# Fri3D_2020_ESP32.net
KiCad netlist of a schematic drawn in Altium Designer
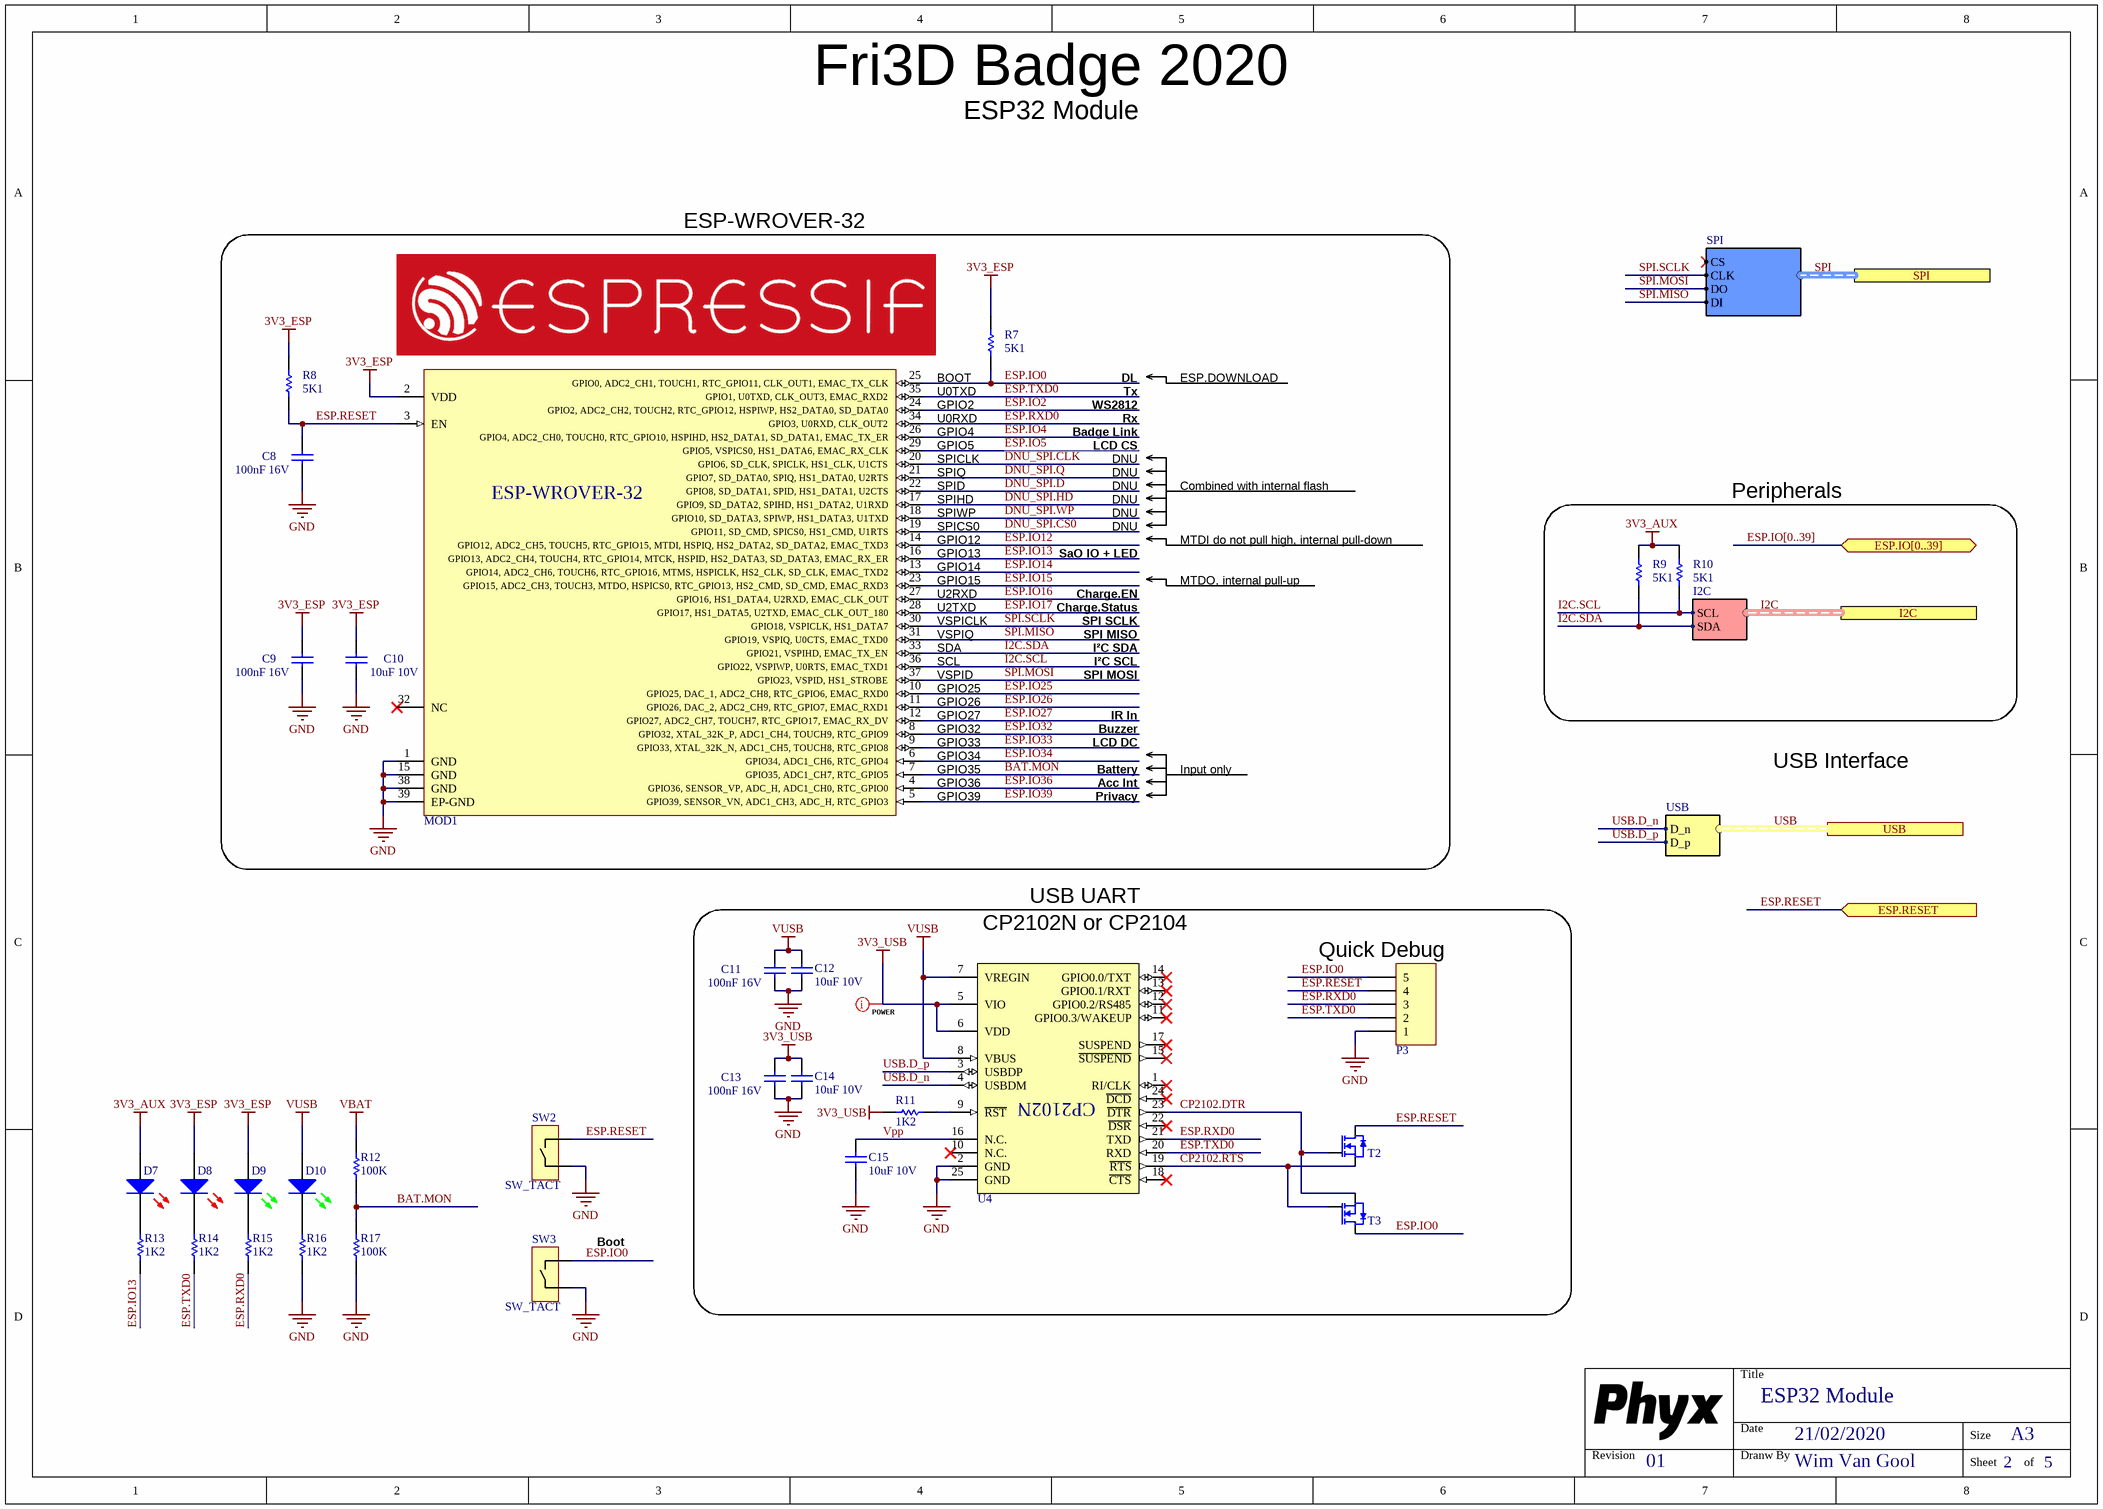
[diagram p0: Fri3D_2020_ESP32.SchDoc]

(export (version "E")
  (design (tool "Eeschema 10.0.6"))
  (components
    (comp (ref "C8")
      (value "100nF 16V")
      (footprint "C0603_N")
      (description "Capacitor Ceramic")
      (libsource (lib "Phyx_Components") (part "CAP_CERAMIC"))
    )
    (comp (ref "C9")
      (value "100nF 16V")
      (footprint "C0603_N")
      (description "Capacitor Ceramic")
      (libsource (lib "Phyx_Components") (part "CAP_CERAMIC"))
    )
    (comp (ref "C10")
      (value "10uF 10V")
      (footprint "C0805_N")
      (description "Capacitor Ceramic")
      (fields (field (name "Comment") "CAP_CERAMIC"))
      (libsource (lib "Phyx_Components") (part "CAP_CERAMIC"))
    )
    (comp (ref "C11")
      (value "100nF 16V")
      (footprint "C0603_N")
      (description "Capacitor Ceramic")
      (libsource (lib "Phyx_Components") (part "CAP_CERAMIC"))
    )
    (comp (ref "C12")
      (value "10uF 10V")
      (footprint "C0805_N")
      (description "Capacitor Ceramic")
      (fields (field (name "Comment") "CAP_CERAMIC"))
      (libsource (lib "Phyx_Components") (part "CAP_CERAMIC"))
    )
    (comp (ref "C13")
      (value "100nF 16V")
      (footprint "C0603_N")
      (description "Capacitor Ceramic")
      (libsource (lib "Phyx_Components") (part "CAP_CERAMIC"))
    )
    (comp (ref "C14")
      (value "10uF 10V")
      (footprint "C0805_N")
      (description "Capacitor Ceramic")
      (fields (field (name "Comment") "CAP_CERAMIC"))
      (libsource (lib "Phyx_Components") (part "CAP_CERAMIC"))
    )
    (comp (ref "C15")
      (value "10uF 10V")
      (footprint "C0805_N")
      (description "Capacitor Ceramic")
      (fields (field (name "Comment") "CAP_CERAMIC"))
      (libsource (lib "Phyx_Components") (part "CAP_CERAMIC"))
    )
    (comp (ref "D7")
      (value "Default 0805 Red LED")
      (footprint "LED_0805_RD")
      (description "=Description")
      (libsource (lib "Phyx_Components") (part "LED_RED"))
    )
    (comp (ref "D8")
      (value "Default 0805 Red LED")
      (footprint "LED_0805_RD")
      (description "=Description")
      (libsource (lib "Phyx_Components") (part "LED_RED"))
    )
    (comp (ref "D9")
      (value "Default 0805 Green LED")
      (footprint "LED_0805_GR")
      (description "=Description")
      (libsource (lib "Phyx_Components") (part "LED_GREEN"))
    )
    (comp (ref "D10")
      (value "Default 0805 Green LED")
      (footprint "LED_0805_GR")
      (description "=Description")
      (libsource (lib "Phyx_Components") (part "LED_GREEN"))
    )
    (comp (ref "MOD1")
      (value "ESP-32 based ESP-WROVER-32")
      (footprint "ESP-WROVER-32")
      (description "WiFi # MOD ESP-WROVER-32")
      (libsource (lib "Phyx_Components") (part "ESP-WROVER-32"))
    )
    (comp (ref "P3")
      (value "Header 1.0mm RA Shrouded 5")
      (footprint "WE_665105131822")
      (libsource (lib "Phyx_Components") (part "Header 5"))
    )
    (comp (ref "R7")
      (value "5K1")
      (footprint "R0603_N")
      (fields (field (name "Comment") "RESISTOR"))
      (libsource (lib "Phyx_Components") (part "RESISTOR"))
    )
    (comp (ref "R8")
      (value "5K1")
      (footprint "R0603_N")
      (fields (field (name "Comment") "RESISTOR"))
      (libsource (lib "Phyx_Components") (part "RESISTOR"))
    )
    (comp (ref "R9")
      (value "5K1")
      (footprint "R0603_N")
      (fields (field (name "Comment") "RESISTOR"))
      (libsource (lib "Phyx_Components") (part "RESISTOR"))
    )
    (comp (ref "R10")
      (value "5K1")
      (footprint "R0603_N")
      (fields (field (name "Comment") "RESISTOR"))
      (libsource (lib "Phyx_Components") (part "RESISTOR"))
    )
    (comp (ref "R11")
      (value "1K2")
      (footprint "R0603_N")
      (fields (field (name "Comment") "RESISTOR"))
      (libsource (lib "Phyx_Components") (part "RESISTOR"))
    )
    (comp (ref "R12")
      (value "100K")
      (footprint "R0603_N")
      (fields (field (name "Comment") "RESISTOR"))
      (libsource (lib "Phyx_Components") (part "RESISTOR"))
    )
    (comp (ref "R13")
      (value "1K2")
      (footprint "R0603_N")
      (fields (field (name "Comment") "RESISTOR"))
      (libsource (lib "Phyx_Components") (part "RESISTOR"))
    )
    (comp (ref "R14")
      (value "1K2")
      (footprint "R0603_N")
      (fields (field (name "Comment") "RESISTOR"))
      (libsource (lib "Phyx_Components") (part "RESISTOR"))
    )
    (comp (ref "R15")
      (value "1K2")
      (footprint "R0603_N")
      (fields (field (name "Comment") "RESISTOR"))
      (libsource (lib "Phyx_Components") (part "RESISTOR"))
    )
    (comp (ref "R16")
      (value "1K2")
      (footprint "R0603_N")
      (fields (field (name "Comment") "RESISTOR"))
      (libsource (lib "Phyx_Components") (part "RESISTOR"))
    )
    (comp (ref "R17")
      (value "100K")
      (footprint "R0603_N")
      (fields (field (name "Comment") "RESISTOR"))
      (libsource (lib "Phyx_Components") (part "RESISTOR"))
    )
    (comp (ref "SW2")
      (value "SW_TACT")
      (footprint "WE_430181038816")
      (libsource (lib "Phyx_Components") (part "SW_TACT"))
    )
    (comp (ref "SW3")
      (value "SW_TACT")
      (footprint "WE_430181038816")
      (libsource (lib "Phyx_Components") (part "SW_TACT"))
    )
    (comp (ref "T2")
      (value "0.2A N-Ch MOSFET Vgs 3.2")
      (footprint "SOT23-3")
      (libsource (lib "Phyx_Components") (part "N_MOSFET_GSD"))
    )
    (comp (ref "T3")
      (value "0.2A N-Ch MOSFET Vgs 3.2")
      (footprint "SOT23-3")
      (libsource (lib "Phyx_Components") (part "N_MOSFET_GSD"))
    )
    (comp (ref "U4")
      (value "USB to UART 3.3-5V")
      (footprint "QFN_24")
      (description "=Description")
      (libsource (lib "Phyx_Components") (part "CP2102N_QFN24"))
    )
  )
  (nets
    (net (code "26") (name "/BAT.MON") (class "Default")
      (node (ref "MOD1") (pin "7") (pinfunction "GPIO35,_ADC1_CH7,_RTC_GPIO5_7") (pintype "input"))
      (node (ref "R12") (pin "2") (pinfunction "2_2") (pintype "passive"))
      (node (ref "R17") (pin "1") (pinfunction "1_1") (pintype "passive"))
    )
    (net (code "27") (name "/CP2102.DTR") (class "Default")
      (node (ref "T2") (pin "1") (pinfunction "G_1") (pintype "passive"))
      (node (ref "T3") (pin "2") (pinfunction "S_2") (pintype "passive"))
      (node (ref "U4") (pin "23") (pinfunction "~{DTR}_23") (pintype "output"))
    )
    (net (code "28") (name "/CP2102.RTS") (class "Default")
      (node (ref "T2") (pin "2") (pinfunction "S_2") (pintype "passive"))
      (node (ref "T3") (pin "1") (pinfunction "G_1") (pintype "passive"))
      (node (ref "U4") (pin "19") (pinfunction "~{RTS}_19") (pintype "output"))
    )
    (net (code "29") (name "/DNU_SPI.CLK") (class "Default")
      (node (ref "MOD1") (pin "20") (pinfunction "GPIO6,_SD_CLK,_SPICLK,_HS1_CLK,_U1CTS_20") (pintype "bidirectional"))
    )
    (net (code "30") (name "/DNU_SPI.CS0") (class "Default")
      (node (ref "MOD1") (pin "19") (pinfunction "GPIO11,_SD_CMD,_SPICS0,_HS1_CMD,_U1RTS_19") (pintype "bidirectional"))
    )
    (net (code "31") (name "/DNU_SPI.D") (class "Default")
      (node (ref "MOD1") (pin "22") (pinfunction "GPIO8,_SD_DATA1,_SPID,_HS1_DATA1,_U2CTS_22") (pintype "bidirectional"))
    )
    (net (code "32") (name "/DNU_SPI.HD") (class "Default")
      (node (ref "MOD1") (pin "17") (pinfunction "GPIO9,_SD_DATA2,_SPIHD,_HS1_DATA2,_U1RXD_17") (pintype "bidirectional"))
    )
    (net (code "33") (name "/DNU_SPI.Q") (class "Default")
      (node (ref "MOD1") (pin "21") (pinfunction "GPIO7,_SD_DATA0,_SPIQ,_HS1_DATA0,_U2RTS_21") (pintype "bidirectional"))
    )
    (net (code "34") (name "/DNU_SPI.WP") (class "Default")
      (node (ref "MOD1") (pin "18") (pinfunction "GPIO10,_SD_DATA3,_SPIWP,_HS1_DATA3,_U1TXD_18") (pintype "bidirectional"))
    )
    (net (code "35") (name "/ESP.IO0") (class "Default")
      (node (ref "MOD1") (pin "25") (pinfunction "GPIO0,_ADC2_CH1,_TOUCH1,_RTC_GPIO11,_CLK_OUT1,_EMAC_TX_CLK_25") (pintype "bidirectional"))
      (node (ref "P3") (pin "5") (pinfunction "5_5") (pintype "passive"))
      (node (ref "R7") (pin "2") (pinfunction "2_2") (pintype "passive"))
      (node (ref "SW3") (pin "1") (pinfunction "1_1") (pintype "passive"))
      (node (ref "T3") (pin "3") (pinfunction "D_3") (pintype "passive"))
    )
    (net (code "36") (name "/ESP.IO2") (class "Default")
      (node (ref "MOD1") (pin "24") (pinfunction "GPIO2,_ADC2_CH2,_TOUCH2,_RTC_GPIO12,_HSPIWP,_HS2_DATA0,_SD_DATA0_24") (pintype "bidirectional"))
    )
    (net (code "37") (name "/ESP.IO4") (class "Default")
      (node (ref "MOD1") (pin "26") (pinfunction "GPIO4,_ADC2_CH0,_TOUCH0,_RTC_GPIO10,_HSPIHD,_HS2_DATA1,_SD_DATA1,_EMAC_TX_ER_26") (pintype "bidirectional"))
    )
    (net (code "38") (name "/ESP.IO5") (class "Default")
      (node (ref "MOD1") (pin "29") (pinfunction "GPIO5,_VSPICS0,_HS1_DATA6,_EMAC_RX_CLK_29") (pintype "bidirectional"))
    )
    (net (code "39") (name "/ESP.IO12") (class "Default")
      (node (ref "MOD1") (pin "14") (pinfunction "GPIO12,_ADC2_CH5,_TOUCH5,_RTC_GPIO15,_MTDI,_HSPIQ,_HS2_DATA2,_SD_DATA2,_EMAC_TXD3_14") (pintype "bidirectional"))
    )
    (net (code "40") (name "/ESP.IO13") (class "Default")
      (node (ref "MOD1") (pin "16") (pinfunction "GPIO13,_ADC2_CH4,_TOUCH4,_RTC_GPIO14,_MTCK,_HSPID,_HS2_DATA3,_SD_DATA3,_EMAC_RX_ER_16") (pintype "bidirectional"))
      (node (ref "R13") (pin "2") (pinfunction "2_2") (pintype "passive"))
    )
    (net (code "41") (name "/ESP.IO14") (class "Default")
      (node (ref "MOD1") (pin "13") (pinfunction "GPIO14,_ADC2_CH6,_TOUCH6,_RTC_GPIO16,_MTMS,_HSPICLK,_HS2_CLK,_SD_CLK,_EMAC_TXD2_13") (pintype "bidirectional"))
    )
    (net (code "42") (name "/ESP.IO15") (class "Default")
      (node (ref "MOD1") (pin "23") (pinfunction "GPIO15,_ADC2_CH3,_TOUCH3,_MTDO,_HSPICS0,_RTC_GPIO13,_HS2_CMD,_SD_CMD,_EMAC_RXD3_23") (pintype "bidirectional"))
    )
    (net (code "43") (name "/ESP.IO16") (class "Default")
      (node (ref "MOD1") (pin "27") (pinfunction "GPIO16,_HS1_DATA4,_U2RXD,_EMAC_CLK_OUT_27") (pintype "bidirectional"))
    )
    (net (code "44") (name "/ESP.IO17") (class "Default")
      (node (ref "MOD1") (pin "28") (pinfunction "GPIO17,_HS1_DATA5,_U2TXD,_EMAC_CLK_OUT_180_28") (pintype "bidirectional"))
    )
    (net (code "45") (name "/ESP.IO25") (class "Default")
      (node (ref "MOD1") (pin "10") (pinfunction "GPIO25,_DAC_1,_ADC2_CH8,_RTC_GPIO6,_EMAC_RXD0_10") (pintype "bidirectional"))
    )
    (net (code "46") (name "/ESP.IO26") (class "Default")
      (node (ref "MOD1") (pin "11") (pinfunction "GPIO26,_DAC_2,_ADC2_CH9,_RTC_GPIO7,_EMAC_RXD1_11") (pintype "bidirectional"))
    )
    (net (code "47") (name "/ESP.IO27") (class "Default")
      (node (ref "MOD1") (pin "12") (pinfunction "GPIO27,_ADC2_CH7,_TOUCH7,_RTC_GPIO17,_EMAC_RX_DV_12") (pintype "bidirectional"))
    )
    (net (code "48") (name "/ESP.IO32") (class "Default")
      (node (ref "MOD1") (pin "8") (pinfunction "GPIO32,_XTAL_32K_P,_ADC1_CH4,_TOUCH9,_RTC_GPIO9_8") (pintype "bidirectional"))
    )
    (net (code "49") (name "/ESP.IO33") (class "Default")
      (node (ref "MOD1") (pin "9") (pinfunction "GPIO33,_XTAL_32K_N,_ADC1_CH5,_TOUCH8,_RTC_GPIO8_9") (pintype "bidirectional"))
    )
    (net (code "50") (name "/ESP.IO34") (class "Default")
      (node (ref "MOD1") (pin "6") (pinfunction "GPIO34,_ADC1_CH6,_RTC_GPIO4_6") (pintype "input"))
    )
    (net (code "51") (name "/ESP.IO36") (class "Default")
      (node (ref "MOD1") (pin "4") (pinfunction "GPIO36,_SENSOR_VP,_ADC_H,_ADC1_CH0,_RTC_GPIO0_4") (pintype "input"))
    )
    (net (code "52") (name "/ESP.IO39") (class "Default")
      (node (ref "MOD1") (pin "5") (pinfunction "GPIO39,_SENSOR_VN,_ADC1_CH3,_ADC_H,_RTC_GPIO3_5") (pintype "input"))
    )
    (net (code "54") (name "/ESP.RESET") (class "Default")
      (node (ref "C8") (pin "1") (pinfunction "1_1") (pintype "passive"))
      (node (ref "MOD1") (pin "3") (pinfunction "EN_3") (pintype "input"))
      (node (ref "P3") (pin "4") (pinfunction "4_4") (pintype "passive"))
      (node (ref "R8") (pin "2") (pinfunction "2_2") (pintype "passive"))
      (node (ref "SW2") (pin "1") (pinfunction "1_1") (pintype "passive"))
      (node (ref "T2") (pin "3") (pinfunction "D_3") (pintype "passive"))
    )
    (net (code "55") (name "/ESP.RXD0") (class "Default")
      (node (ref "MOD1") (pin "34") (pinfunction "GPIO3,_U0RXD,_CLK_OUT2_34") (pintype "bidirectional"))
      (node (ref "P3") (pin "3") (pinfunction "3_3") (pintype "passive"))
      (node (ref "R15") (pin "2") (pinfunction "2_2") (pintype "passive"))
      (node (ref "U4") (pin "21") (pinfunction "TXD_21") (pintype "output"))
    )
    (net (code "56") (name "/ESP.TXD0") (class "Default")
      (node (ref "MOD1") (pin "35") (pinfunction "GPIO1,_U0TXD,_CLK_OUT3,_EMAC_RXD2_35") (pintype "bidirectional"))
      (node (ref "P3") (pin "2") (pinfunction "2_2") (pintype "passive"))
      (node (ref "R14") (pin "2") (pinfunction "2_2") (pintype "passive"))
      (node (ref "U4") (pin "20") (pinfunction "RXD_20") (pintype "input"))
    )
    (net (code "57") (name "/I2C.SCL") (class "Default")
      (node (ref "MOD1") (pin "36") (pinfunction "GPIO22,_VSPIWP,_U0RTS,_EMAC_TXD1_36") (pintype "bidirectional"))
      (node (ref "R10") (pin "2") (pinfunction "2_2") (pintype "passive"))
    )
    (net (code "58") (name "/I2C.SDA") (class "Default")
      (node (ref "MOD1") (pin "33") (pinfunction "GPIO21,_VSPIHD,_EMAC_TX_EN_33") (pintype "bidirectional"))
      (node (ref "R9") (pin "2") (pinfunction "2_2") (pintype "passive"))
    )
    (net (code "60") (name "/SPI.MISO") (class "Default")
      (node (ref "MOD1") (pin "31") (pinfunction "GPIO19,_VSPIQ,_U0CTS,_EMAC_TXD0_31") (pintype "bidirectional"))
    )
    (net (code "61") (name "/SPI.MOSI") (class "Default")
      (node (ref "MOD1") (pin "37") (pinfunction "GPIO23,_VSPID,_HS1_STROBE_37") (pintype "bidirectional"))
    )
    (net (code "62") (name "/SPI.SCLK") (class "Default")
      (node (ref "MOD1") (pin "30") (pinfunction "GPIO18,_VSPICLK,_HS1_DATA7_30") (pintype "bidirectional"))
    )
    (net (code "64") (name "/USB.D_n") (class "Default")
      (node (ref "U4") (pin "4") (pinfunction "USBDM_4") (pintype "bidirectional"))
    )
    (net (code "65") (name "/USB.D_p") (class "Default")
      (node (ref "U4") (pin "3") (pinfunction "USBDP_3") (pintype "bidirectional"))
    )
    (net (code "67") (name "/Vpp") (class "Default")
      (node (ref "C15") (pin "2") (pinfunction "2_2") (pintype "passive"))
      (node (ref "U4") (pin "16") (pinfunction "N.C._16") (pintype "passive"))
    )
    (net (code "68") (name "3V3_AUX") (class "Default")
      (node (ref "D7") (pin "1") (pinfunction "A_1") (pintype "passive"))
      (node (ref "R10") (pin "1") (pinfunction "1_1") (pintype "passive"))
      (node (ref "R9") (pin "1") (pinfunction "1_1") (pintype "passive"))
    )
    (net (code "69") (name "3V3_ESP") (class "Default")
      (node (ref "C10") (pin "1") (pinfunction "1_1") (pintype "passive"))
      (node (ref "C9") (pin "1") (pinfunction "1_1") (pintype "passive"))
      (node (ref "D8") (pin "1") (pinfunction "A_1") (pintype "passive"))
      (node (ref "D9") (pin "1") (pinfunction "A_1") (pintype "passive"))
      (node (ref "MOD1") (pin "2") (pinfunction "VDD_2") (pintype "power_in"))
      (node (ref "R7") (pin "1") (pinfunction "1_1") (pintype "passive"))
      (node (ref "R8") (pin "1") (pinfunction "1_1") (pintype "passive"))
    )
    (net (code "70") (name "3V3_USB") (class "Default")
      (node (ref "C13") (pin "1") (pinfunction "1_1") (pintype "passive"))
      (node (ref "C14") (pin "2") (pinfunction "2_2") (pintype "passive"))
      (node (ref "R11") (pin "1") (pinfunction "1_1") (pintype "passive"))
      (node (ref "U4") (pin "5") (pinfunction "VIO_5") (pintype "power_in"))
      (node (ref "U4") (pin "6") (pinfunction "VDD_6") (pintype "power_in"))
    )
    (net (code "71") (name "GND") (class "Default")
      (node (ref "C10") (pin "2") (pinfunction "2_2") (pintype "passive"))
      (node (ref "C11") (pin "2") (pinfunction "2_2") (pintype "passive"))
      (node (ref "C12") (pin "1") (pinfunction "1_1") (pintype "passive"))
      (node (ref "C13") (pin "2") (pinfunction "2_2") (pintype "passive"))
      (node (ref "C14") (pin "1") (pinfunction "1_1") (pintype "passive"))
      (node (ref "C15") (pin "1") (pinfunction "1_1") (pintype "passive"))
      (node (ref "C8") (pin "2") (pinfunction "2_2") (pintype "passive"))
      (node (ref "C9") (pin "2") (pinfunction "2_2") (pintype "passive"))
      (node (ref "MOD1") (pin "1") (pinfunction "GND_1") (pintype "power_in"))
      (node (ref "MOD1") (pin "15") (pinfunction "GND_15") (pintype "power_in"))
      (node (ref "MOD1") (pin "38") (pinfunction "GND_38") (pintype "power_in"))
      (node (ref "MOD1") (pin "39") (pinfunction "EP-GND_39") (pintype "power_in"))
      (node (ref "P3") (pin "1") (pinfunction "1_1") (pintype "passive"))
      (node (ref "R16") (pin "2") (pinfunction "2_2") (pintype "passive"))
      (node (ref "R17") (pin "2") (pinfunction "2_2") (pintype "passive"))
      (node (ref "SW2") (pin "2") (pinfunction "2_2") (pintype "passive"))
      (node (ref "SW3") (pin "2") (pinfunction "2_2") (pintype "passive"))
      (node (ref "U4") (pin "2") (pinfunction "GND_2") (pintype "power_in"))
      (node (ref "U4") (pin "25") (pinfunction "GND_25") (pintype "power_in"))
    )
    (net (code "72") (name "Net-(D7-K)") (class "Default")
      (node (ref "D7") (pin "2") (pinfunction "K_2") (pintype "passive"))
      (node (ref "R13") (pin "1") (pinfunction "1_1") (pintype "passive"))
    )
    (net (code "73") (name "Net-(D8-K)") (class "Default")
      (node (ref "D8") (pin "2") (pinfunction "K_2") (pintype "passive"))
      (node (ref "R14") (pin "1") (pinfunction "1_1") (pintype "passive"))
    )
    (net (code "74") (name "Net-(D9-K)") (class "Default")
      (node (ref "D9") (pin "2") (pinfunction "K_2") (pintype "passive"))
      (node (ref "R15") (pin "1") (pinfunction "1_1") (pintype "passive"))
    )
    (net (code "75") (name "Net-(D10-K)") (class "Default")
      (node (ref "D10") (pin "2") (pinfunction "K_2") (pintype "passive"))
      (node (ref "R16") (pin "1") (pinfunction "1_1") (pintype "passive"))
    )
    (net (code "76") (name "Net-(U4-~{RST})") (class "Default")
      (node (ref "R11") (pin "2") (pinfunction "2_2") (pintype "passive"))
      (node (ref "U4") (pin "9") (pinfunction "~{RST}_9") (pintype "input"))
    )
    (net (code "77") (name "VBAT") (class "Default")
      (node (ref "R12") (pin "1") (pinfunction "1_1") (pintype "passive"))
    )
    (net (code "78") (name "VUSB") (class "Default")
      (node (ref "C11") (pin "1") (pinfunction "1_1") (pintype "passive"))
      (node (ref "C12") (pin "2") (pinfunction "2_2") (pintype "passive"))
      (node (ref "D10") (pin "1") (pinfunction "A_1") (pintype "passive"))
      (node (ref "U4") (pin "7") (pinfunction "VREGIN_7") (pintype "power_in"))
      (node (ref "U4") (pin "8") (pinfunction "VBUS_8") (pintype "input"))
    )
    (net (code "79") (name "unconnected-(MOD1-NC-Pad32)") (class "Default")
      (node (ref "MOD1") (pin "32") (pinfunction "NC_32") (pintype "passive+no_connect"))
    )
    (net (code "80") (name "unconnected-(U4-GPIO0.0{slash}TXT-Pad14)") (class "Default")
      (node (ref "U4") (pin "14") (pinfunction "GPIO0.0/TXT_14") (pintype "bidirectional+no_connect"))
    )
    (net (code "81") (name "unconnected-(U4-GPIO0.1{slash}RXT-Pad13)") (class "Default")
      (node (ref "U4") (pin "13") (pinfunction "GPIO0.1/RXT_13") (pintype "bidirectional+no_connect"))
    )
    (net (code "82") (name "unconnected-(U4-GPIO0.2{slash}RS485-Pad12)") (class "Default")
      (node (ref "U4") (pin "12") (pinfunction "GPIO0.2/RS485_12") (pintype "bidirectional+no_connect"))
    )
    (net (code "83") (name "unconnected-(U4-GPIO0.3{slash}WAKEUP-Pad11)") (class "Default")
      (node (ref "U4") (pin "11") (pinfunction "GPIO0.3/WAKEUP_11") (pintype "bidirectional+no_connect"))
    )
    (net (code "84") (name "unconnected-(U4-N.C.-Pad10)") (class "Default")
      (node (ref "U4") (pin "10") (pinfunction "N.C._10") (pintype "passive+no_connect"))
    )
    (net (code "85") (name "unconnected-(U4-RI{slash}CLK-Pad1)") (class "Default")
      (node (ref "U4") (pin "1") (pinfunction "RI/CLK_1") (pintype "bidirectional+no_connect"))
    )
    (net (code "86") (name "unconnected-(U4-SUSPEND-Pad17)") (class "Default")
      (node (ref "U4") (pin "17") (pinfunction "SUSPEND_17") (pintype "output+no_connect"))
    )
    (net (code "87") (name "unconnected-(U4-~{CTS}-Pad18)") (class "Default")
      (node (ref "U4") (pin "18") (pinfunction "~{CTS}_18") (pintype "input+no_connect"))
    )
    (net (code "88") (name "unconnected-(U4-~{DCD}-Pad24)") (class "Default")
      (node (ref "U4") (pin "24") (pinfunction "~{DCD}_24") (pintype "input+no_connect"))
    )
    (net (code "89") (name "unconnected-(U4-~{DSR}-Pad22)") (class "Default")
      (node (ref "U4") (pin "22") (pinfunction "~{DSR}_22") (pintype "input+no_connect"))
    )
    (net (code "90") (name "unconnected-(U4-~{SUSPEND}-Pad15)") (class "Default")
      (node (ref "U4") (pin "15") (pinfunction "~{SUSPEND}_15") (pintype "output+no_connect"))
    )
  )
)
